# primary_EEPROM_and_T.net
KiCad netlist of a schematic drawn in Altium Designer
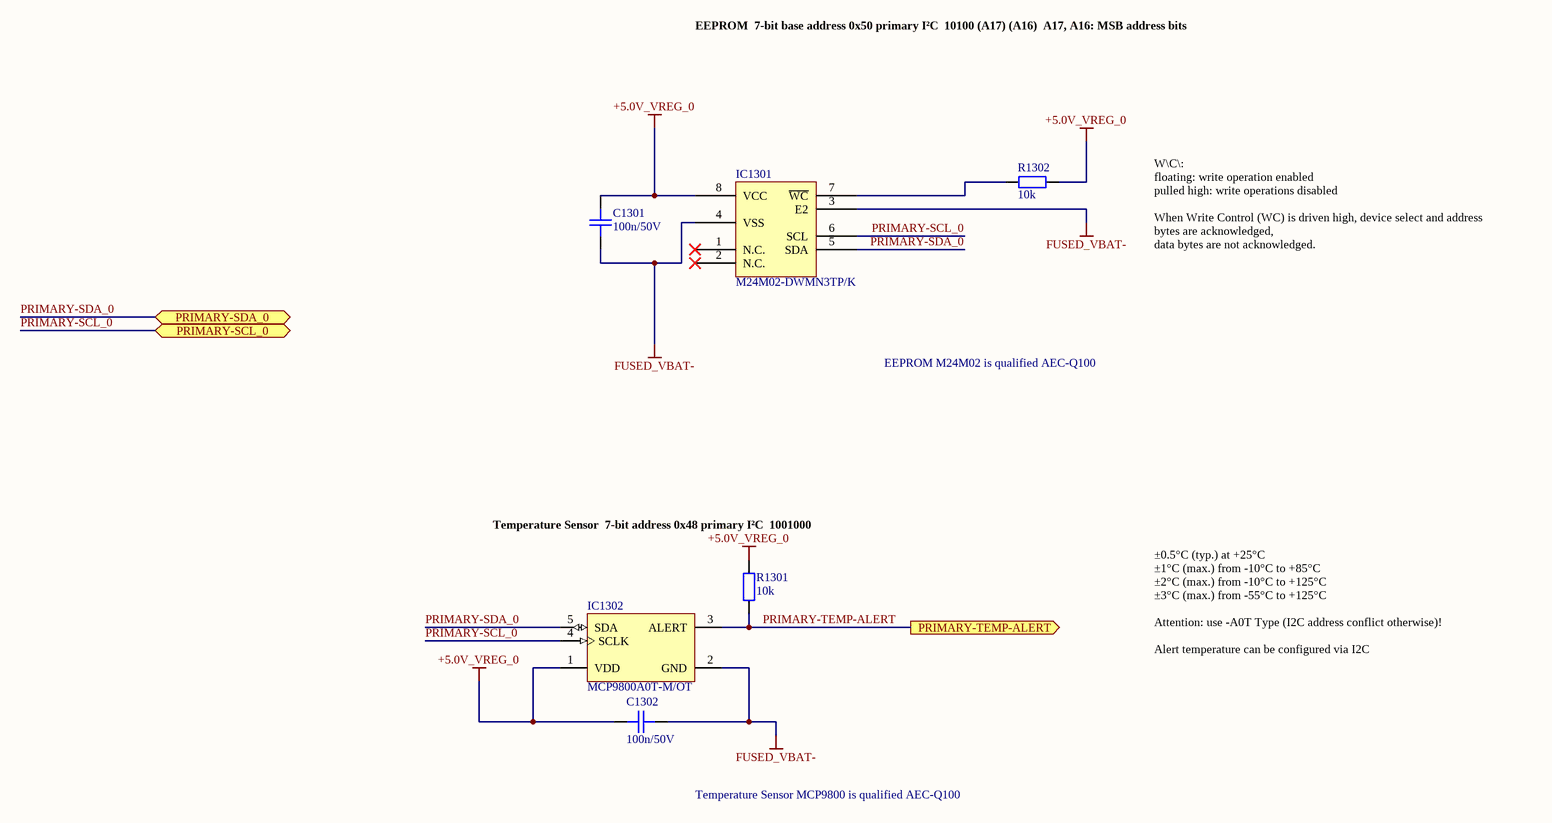
[diagram p0: primary_EEPROM_and_T.SchDoc]

(export (version "E")
  (design (tool "Eeschema 10.0.6"))
  (components
    (comp (ref "C1301")
      (value "100n/50V")
      (footprint "CAPC1608X08N")
      (description "MLCC")
      (fields (field (name "PART NUMBER") "gen_C_ceramic_100n_50V_X7R_0603"))
      (libsource (lib "OE750") (part "C"))
    )
    (comp (ref "C1302")
      (value "100n/50V")
      (footprint "CAPC1608X08N")
      (description "MLCC")
      (fields (field (name "PART NUMBER") "gen_C_ceramic_100n_50V_X7R_0603"))
      (libsource (lib "OE750") (part "C"))
    )
    (comp (ref "IC1301")
      (value "M24M02-DWMN3TP/K")
      (footprint "SOIC127P600X175-8N")
      (description "Automotive 2-Mbit serial I²C \r\nbus EEPROM with 1 MHz clock")
      (fields (field (name "MANUFACTURER") "STMicroelectronics"))
      (libsource (lib "OE750") (part "M24M02-DWMN3TP/K"))
    )
    (comp (ref "IC1302")
      (value "MCP9800A0T-M/OT")
      (footprint "SOT-23-OT5_L")
      (libsource (lib "Altium Content Vault") (part "SEN-TEMP-MCP980X-5"))
    )
    (comp (ref "R1301")
      (value "10k")
      (footprint "RESC1608X05N")
      (description "SMD Resistor 10k 0603")
      (fields (field (name "PART NUMBER") "gen_R_10k_0603") (field (name "TOLERANCE") "1%"))
      (libsource (lib "OE750") (part "R"))
    )
    (comp (ref "R1302")
      (value "10k")
      (footprint "RESC1608X05N")
      (description "SMD Resistor 10k 0603")
      (fields (field (name "PART NUMBER") "gen_R_10k_0603") (field (name "TOLERANCE") "1%"))
      (libsource (lib "OE750") (part "R"))
    )
  )
  (nets
    (net (code "1") (name "+5.0V_VREG_0") (class "Default")
      (node (ref "C1301") (pin "2") (pinfunction "2_2") (pintype "passive"))
      (node (ref "C1302") (pin "2") (pinfunction "2_2") (pintype "passive"))
      (node (ref "IC1301") (pin "8") (pinfunction "VCC_8") (pintype "power_in"))
      (node (ref "IC1302") (pin "1") (pinfunction "VDD_1") (pintype "power_in"))
      (node (ref "R1301") (pin "2") (pinfunction "2_2") (pintype "passive"))
      (node (ref "R1302") (pin "2") (pinfunction "2_2") (pintype "passive"))
    )
    (net (code "2") (name "/PRIMARY-SCL_0") (class "Default")
      (node (ref "IC1301") (pin "6") (pinfunction "SCL_6") (pintype "passive"))
      (node (ref "IC1302") (pin "4") (pinfunction "SCLK_4") (pintype "input"))
    )
    (net (code "3") (name "/PRIMARY-SDA_0") (class "Default")
      (node (ref "IC1301") (pin "5") (pinfunction "SDA_5") (pintype "passive"))
      (node (ref "IC1302") (pin "5") (pinfunction "SDA_5") (pintype "bidirectional"))
    )
    (net (code "4") (name "/PRIMARY-TEMP-ALERT") (class "Default")
      (node (ref "IC1302") (pin "3") (pinfunction "ALERT_3") (pintype "open_collector"))
      (node (ref "R1301") (pin "1") (pinfunction "1_1") (pintype "passive"))
    )
    (net (code "5") (name "FUSED_VBAT-") (class "Default")
      (node (ref "C1301") (pin "1") (pinfunction "1_1") (pintype "passive"))
      (node (ref "C1302") (pin "1") (pinfunction "1_1") (pintype "passive"))
      (node (ref "IC1301") (pin "3") (pinfunction "E2_3") (pintype "passive"))
      (node (ref "IC1301") (pin "4") (pinfunction "VSS_4") (pintype "power_in"))
      (node (ref "IC1302") (pin "2") (pinfunction "GND_2") (pintype "power_in"))
    )
    (net (code "6") (name "Net-(IC1301-~{WC})") (class "Default")
      (node (ref "IC1301") (pin "7") (pinfunction "~{WC}_7") (pintype "passive"))
      (node (ref "R1302") (pin "1") (pinfunction "1_1") (pintype "passive"))
    )
    (net (code "7") (name "unconnected-(IC1301-N.C.-Pad1)") (class "Default")
      (node (ref "IC1301") (pin "1") (pinfunction "N.C._1") (pintype "passive+no_connect"))
    )
    (net (code "8") (name "unconnected-(IC1301-N.C.-Pad2)") (class "Default")
      (node (ref "IC1301") (pin "2") (pinfunction "N.C._2") (pintype "passive+no_connect"))
    )
  )
)
